# dual-tda1543-dac.net
KiCad netlist of a schematic drawn in EAGLE
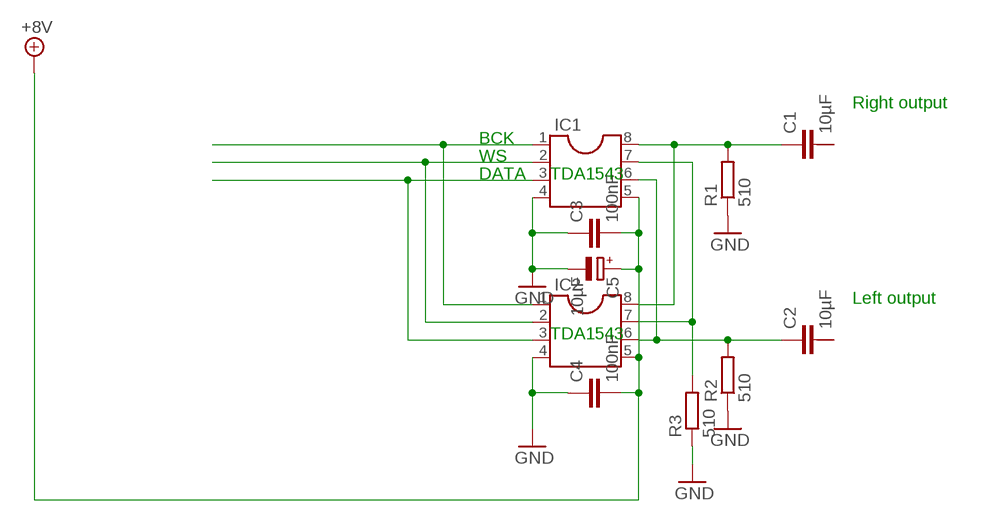
[diagram p0: schematic, sheet 1]

(export (version "E")
  (design (tool "Eeschema 10.0.6"))
  (components
    (comp (ref "C1")
      (value "10µF")
      (footprint "eagle-import:C10-15B6")
      (libsource (lib "eagle-import") (part "C-10-15/6"))
    )
    (comp (ref "C2")
      (value "10µF")
      (footprint "eagle-import:C10-15B6")
      (libsource (lib "eagle-import") (part "C-10-15/6"))
    )
    (comp (ref "C3")
      (value "100nF")
      (footprint "eagle-import:C025-024X044")
      (libsource (lib "eagle-import") (part "C-EU025-024X044"))
    )
    (comp (ref "C4")
      (value "100nF")
      (footprint "eagle-import:C025-024X044")
      (libsource (lib "eagle-import") (part "C-EU025-024X044"))
    )
    (comp (ref "C5")
      (value "10µF")
      (footprint "eagle-import:E3,5-8")
      (libsource (lib "eagle-import") (part "CPOL-EUE3.5-8"))
    )
    (comp (ref "IC1")
      (value "TDA1543S")
      (footprint "eagle-import:SOCKED-08")
      (libsource (lib "eagle-import") (part "TDA1543S"))
    )
    (comp (ref "IC2")
      (value "TDA1543S")
      (footprint "eagle-import:SOCKED-08")
      (libsource (lib "eagle-import") (part "TDA1543S"))
    )
    (comp (ref "R1")
      (value "510")
      (footprint "eagle-import:0207_7")
      (libsource (lib "eagle-import") (part "R-EU_0207/7"))
    )
    (comp (ref "R2")
      (value "510")
      (footprint "eagle-import:0207_7")
      (libsource (lib "eagle-import") (part "R-EU_0207/7"))
    )
    (comp (ref "R3")
      (value "510")
      (footprint "eagle-import:0207_7")
      (libsource (lib "eagle-import") (part "R-EU_0207/7"))
    )
  )
  (nets
    (net (code "1") (name "+8V") (class "Default")
      (node (ref "C3") (pin "2") (pinfunction "2_2") (pintype "passive"))
      (node (ref "C4") (pin "2") (pinfunction "2_2") (pintype "passive"))
      (node (ref "C5") (pin "+") (pinfunction "+_+") (pintype "passive"))
      (node (ref "IC1") (pin "5") (pinfunction "AOR_5") (pintype "passive"))
      (node (ref "IC2") (pin "5") (pinfunction "AOR_5") (pintype "passive"))
    )
    (net (code "2") (name "GND") (class "Default")
      (node (ref "C3") (pin "1") (pinfunction "1_1") (pintype "passive"))
      (node (ref "C4") (pin "1") (pinfunction "1_1") (pintype "passive"))
      (node (ref "C5") (pin "-") (pinfunction "-_-") (pintype "passive"))
      (node (ref "IC1") (pin "4") (pinfunction "GND_4") (pintype "passive"))
      (node (ref "IC2") (pin "4") (pinfunction "GND_4") (pintype "passive"))
      (node (ref "R1") (pin "1") (pinfunction "1_1") (pintype "passive"))
      (node (ref "R2") (pin "1") (pinfunction "1_1") (pintype "passive"))
      (node (ref "R3") (pin "1") (pinfunction "1_1") (pintype "passive"))
    )
    (net (code "3") (name "Net-(IC1-AOL)") (class "Default")
      (node (ref "IC1") (pin "7") (pinfunction "AOL_7") (pintype "passive"))
      (node (ref "IC2") (pin "7") (pinfunction "AOL_7") (pintype "passive"))
      (node (ref "R3") (pin "2") (pinfunction "2_2") (pintype "passive"))
    )
    (net (code "4") (name "Net-(IC1-BCK)") (class "Default")
      (node (ref "IC1") (pin "1") (pinfunction "BCK_1") (pintype "passive"))
      (node (ref "IC2") (pin "1") (pinfunction "BCK_1") (pintype "passive"))
    )
    (net (code "5") (name "Net-(IC1-DATA)") (class "Default")
      (node (ref "IC1") (pin "3") (pinfunction "DATA_3") (pintype "passive"))
      (node (ref "IC2") (pin "3") (pinfunction "DATA_3") (pintype "passive"))
    )
    (net (code "6") (name "Net-(IC1-VDD)") (class "Default")
      (node (ref "C1") (pin "1") (pinfunction "1_1") (pintype "passive"))
      (node (ref "IC1") (pin "8") (pinfunction "VDD_8") (pintype "passive"))
      (node (ref "IC2") (pin "8") (pinfunction "VDD_8") (pintype "passive"))
      (node (ref "R1") (pin "2") (pinfunction "2_2") (pintype "passive"))
    )
    (net (code "7") (name "Net-(IC1-VREF)") (class "Default")
      (node (ref "C2") (pin "1") (pinfunction "1_1") (pintype "passive"))
      (node (ref "IC1") (pin "6") (pinfunction "VREF_6") (pintype "passive"))
      (node (ref "IC2") (pin "6") (pinfunction "VREF_6") (pintype "passive"))
      (node (ref "R2") (pin "2") (pinfunction "2_2") (pintype "passive"))
    )
    (net (code "8") (name "Net-(IC1-WS)") (class "Default")
      (node (ref "IC1") (pin "2") (pinfunction "WS_2") (pintype "passive"))
      (node (ref "IC2") (pin "2") (pinfunction "WS_2") (pintype "passive"))
    )
    (net (code "9") (name "unconnected-(C1-Pad2)") (class "Default")
      (node (ref "C1") (pin "2") (pinfunction "2_2") (pintype "passive"))
    )
    (net (code "10") (name "unconnected-(C1-Pad3)") (class "Default")
      (node (ref "C1") (pin "3") (pinfunction "3_3") (pintype "passive"))
    )
    (net (code "11") (name "unconnected-(C2-Pad2)") (class "Default")
      (node (ref "C2") (pin "2") (pinfunction "2_2") (pintype "passive"))
    )
    (net (code "12") (name "unconnected-(C2-Pad3)") (class "Default")
      (node (ref "C2") (pin "3") (pinfunction "3_3") (pintype "passive"))
    )
  )
)
